# design.net
KiCad netlist of a schematic drawn in EasyEDA
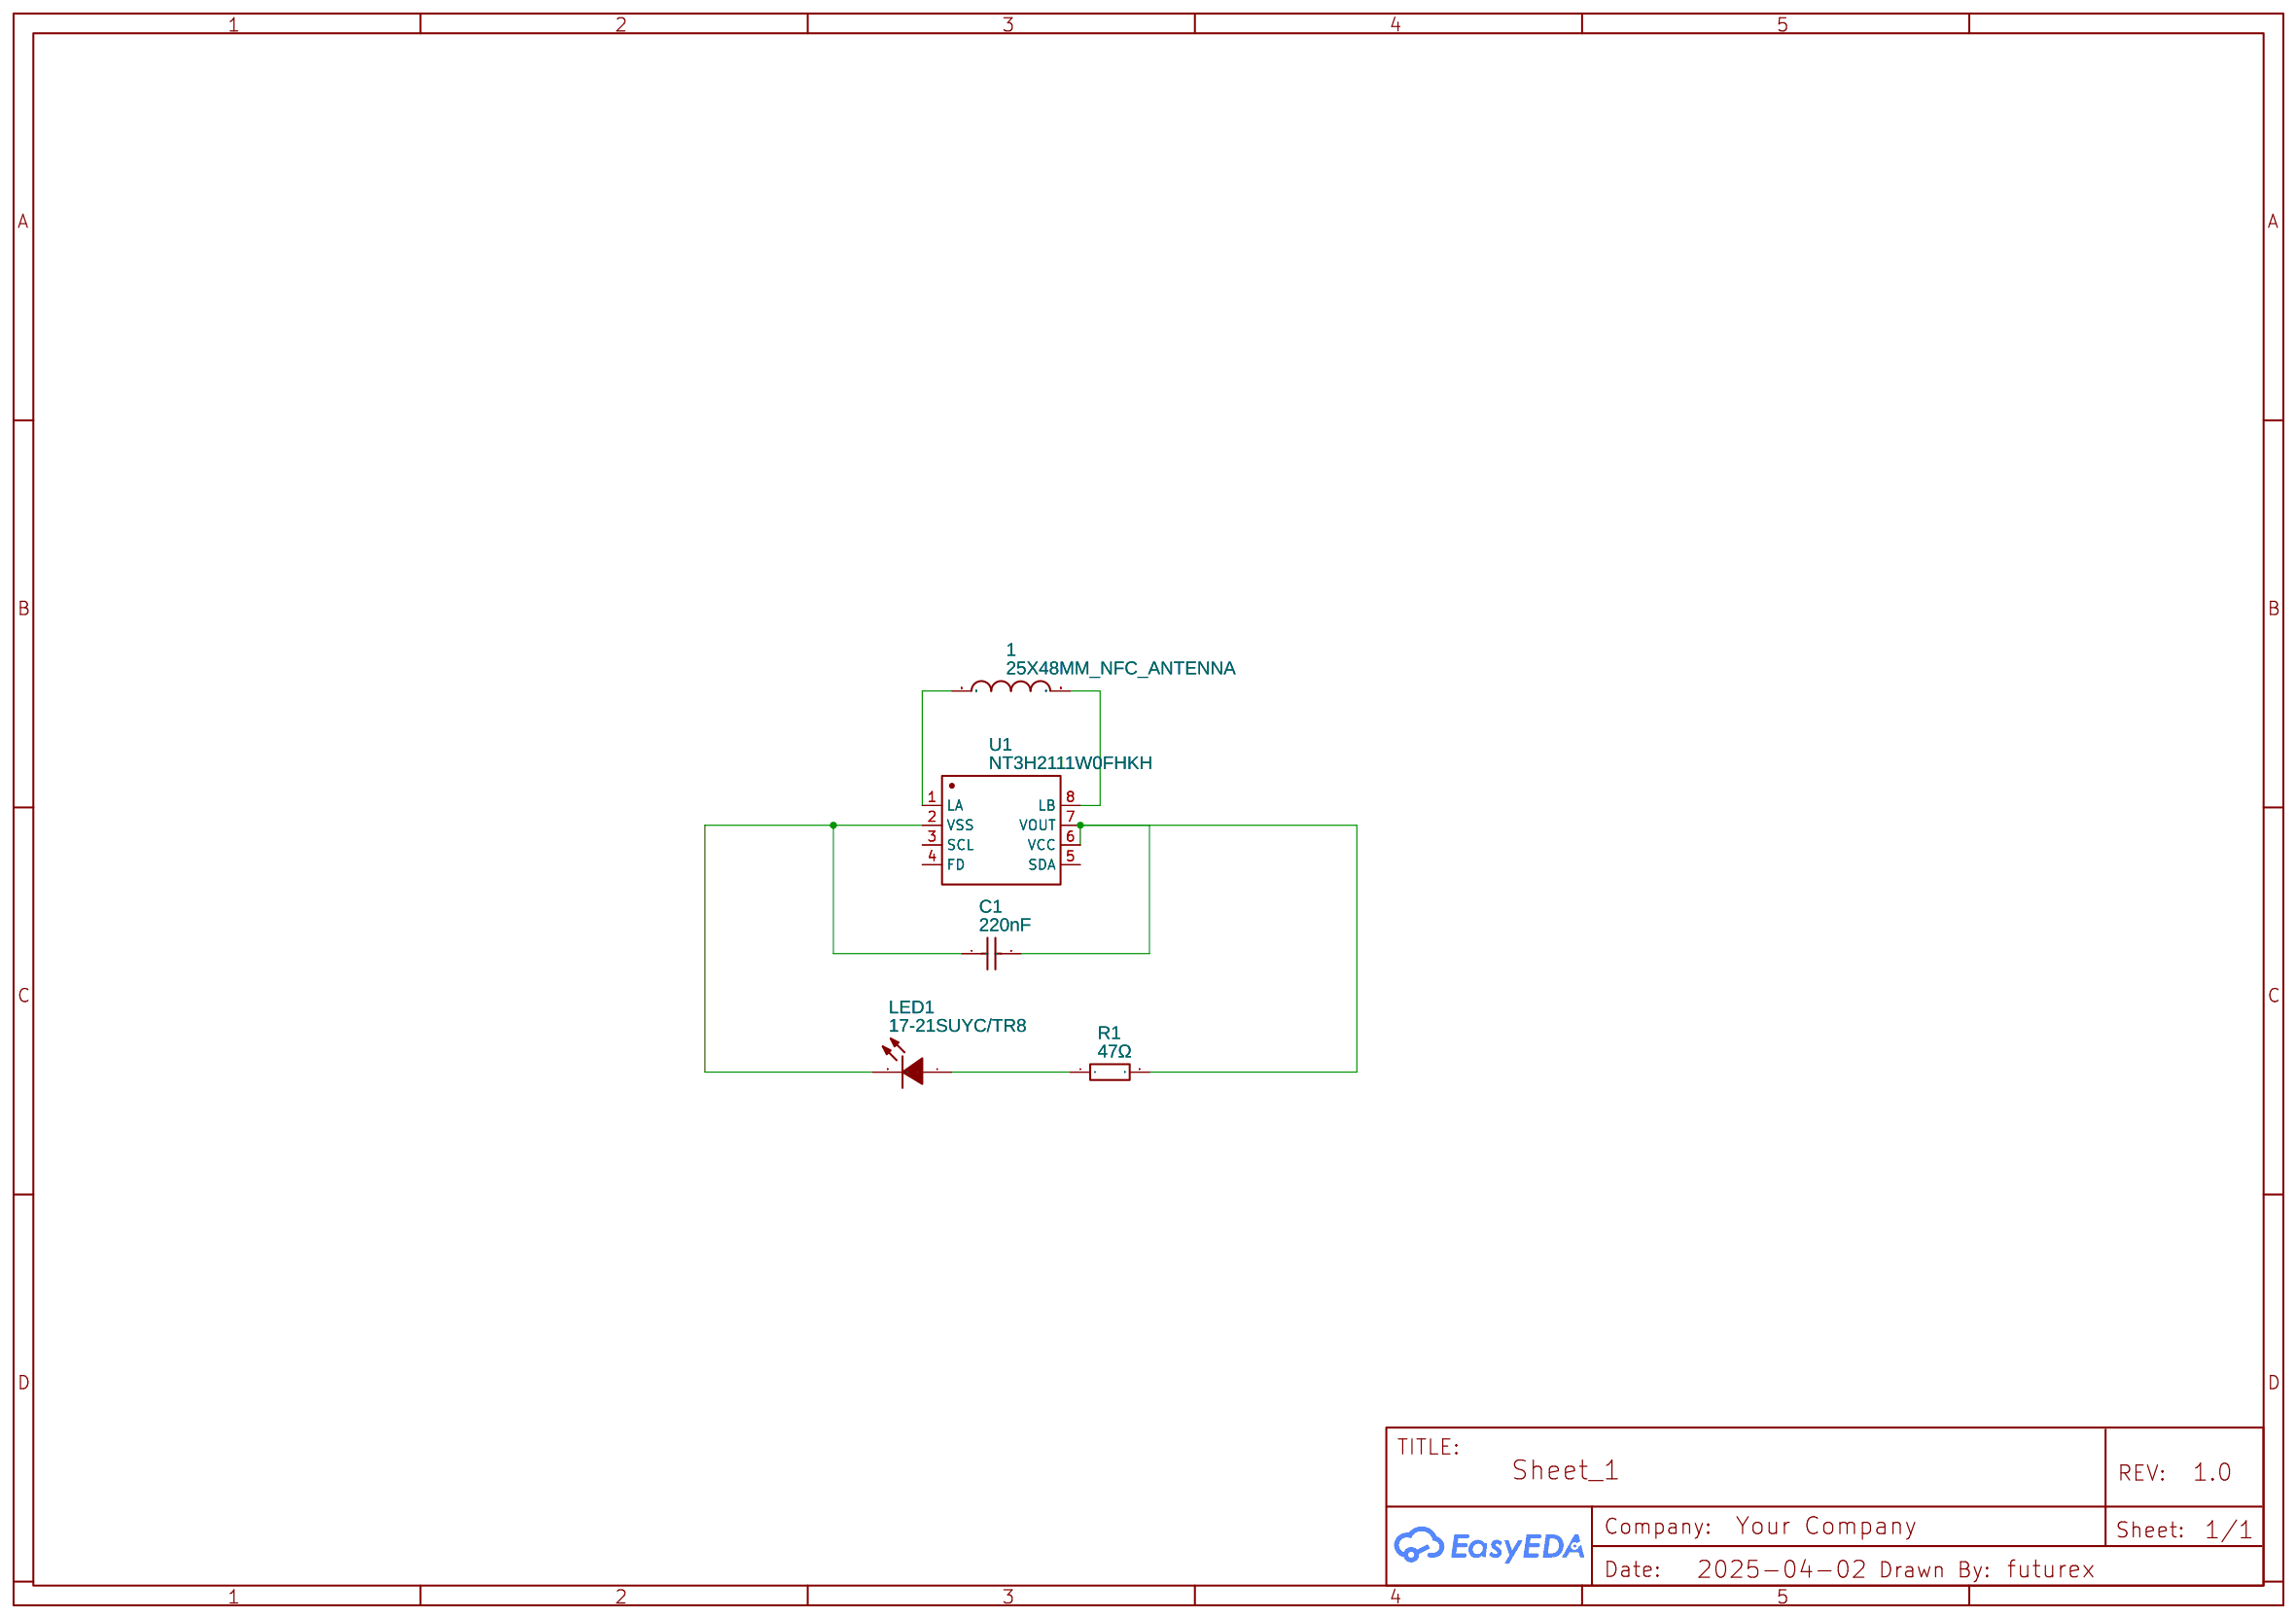
[diagram p0: schematic sheet]

(export (version "E")
  (design (tool "Eeschema 10.0.6"))
  (components
    (comp (ref "1") (value "25X48MM_NFC_ANTENNA") (libsource (lib "") (part "25X48MM_NFC_ANTENNA")))
    (comp (ref "C1")
      (value "220nF")
      (fields
        (field (name "Manufacturer Part") "CL10B224KA8NNNC")
        (field (name "Manufacturer") "SAMSUNG(三星)")
      )
      (libsource (lib "") (part "CL10B224KA8NNNC"))
    )
    (comp (ref "LED1")
      (value "17-21SUYC/TR8")
      (fields (field (name "Manufacturer Part") "KT-0805黄灯") (field (name "Manufacturer") "KENTO"))
      (libsource (lib "") (part "17-21SUYC/TR8"))
    )
    (comp (ref "R1")
      (value "47Ω")
      (fields
        (field (name "Manufacturer Part") "0603WAF470JT5E")
        (field (name "Manufacturer") "UNI-ROYAL(厚声)")
      )
      (libsource (lib "") (part "0603WAF470JT5E"))
    )
    (comp (ref "U1")
      (value "NT3H2111W0FHKH")
      (fields (field (name "Manufacturer") "NXP(恩智浦)"))
      (libsource (lib "") (part "NT3H2111W0FHKH"))
    )
  )
  (nets
    (net (code "1") (name "Net-(LED1-+)") (class "Default")
      (node (ref "LED1") (pin "1") (pinfunction "+_1") (pintype "unspecified"))
      (node (ref "R1") (pin "1") (pinfunction "1_1") (pintype "input"))
    )
    (net (code "2") (name "Net-(LED1--)") (class "Default")
      (node (ref "C1") (pin "1") (pinfunction "1_1") (pintype "input"))
      (node (ref "LED1") (pin "2") (pinfunction "-_2") (pintype "unspecified"))
      (node (ref "U1") (pin "2") (pinfunction "VSS_2") (pintype "unspecified"))
    )
    (net (code "3") (name "Net-(U1-LA)") (class "Default")
      (node (ref "1") (pin "P$1") (pinfunction "P$1_P$1") (pintype "bidirectional"))
      (node (ref "U1") (pin "1") (pinfunction "LA_1") (pintype "unspecified"))
    )
    (net (code "4") (name "Net-(U1-LB)") (class "Default")
      (node (ref "1") (pin "P$2") (pinfunction "P$2_P$2") (pintype "bidirectional"))
      (node (ref "U1") (pin "8") (pinfunction "LB_8") (pintype "unspecified"))
    )
    (net (code "5") (name "Net-(U1-VCC)") (class "Default")
      (node (ref "C1") (pin "2") (pinfunction "2_2") (pintype "input"))
      (node (ref "R1") (pin "2") (pinfunction "2_2") (pintype "input"))
      (node (ref "U1") (pin "6") (pinfunction "VCC_6") (pintype "unspecified"))
      (node (ref "U1") (pin "7") (pinfunction "VOUT_7") (pintype "unspecified"))
    )
    (net (code "6") (name "unconnected-(U1-FD-Pad4)") (class "Default")
      (node (ref "U1") (pin "4") (pinfunction "FD_4") (pintype "unspecified"))
    )
    (net (code "7") (name "unconnected-(U1-SCL-Pad3)") (class "Default")
      (node (ref "U1") (pin "3") (pinfunction "SCL_3") (pintype "unspecified"))
    )
    (net (code "8") (name "unconnected-(U1-SDA-Pad5)") (class "Default")
      (node (ref "U1") (pin "5") (pinfunction "SDA_5") (pintype "unspecified"))
    )
  )
)
